# pc_shield.net
KiCad netlist of a schematic drawn in EAGLE
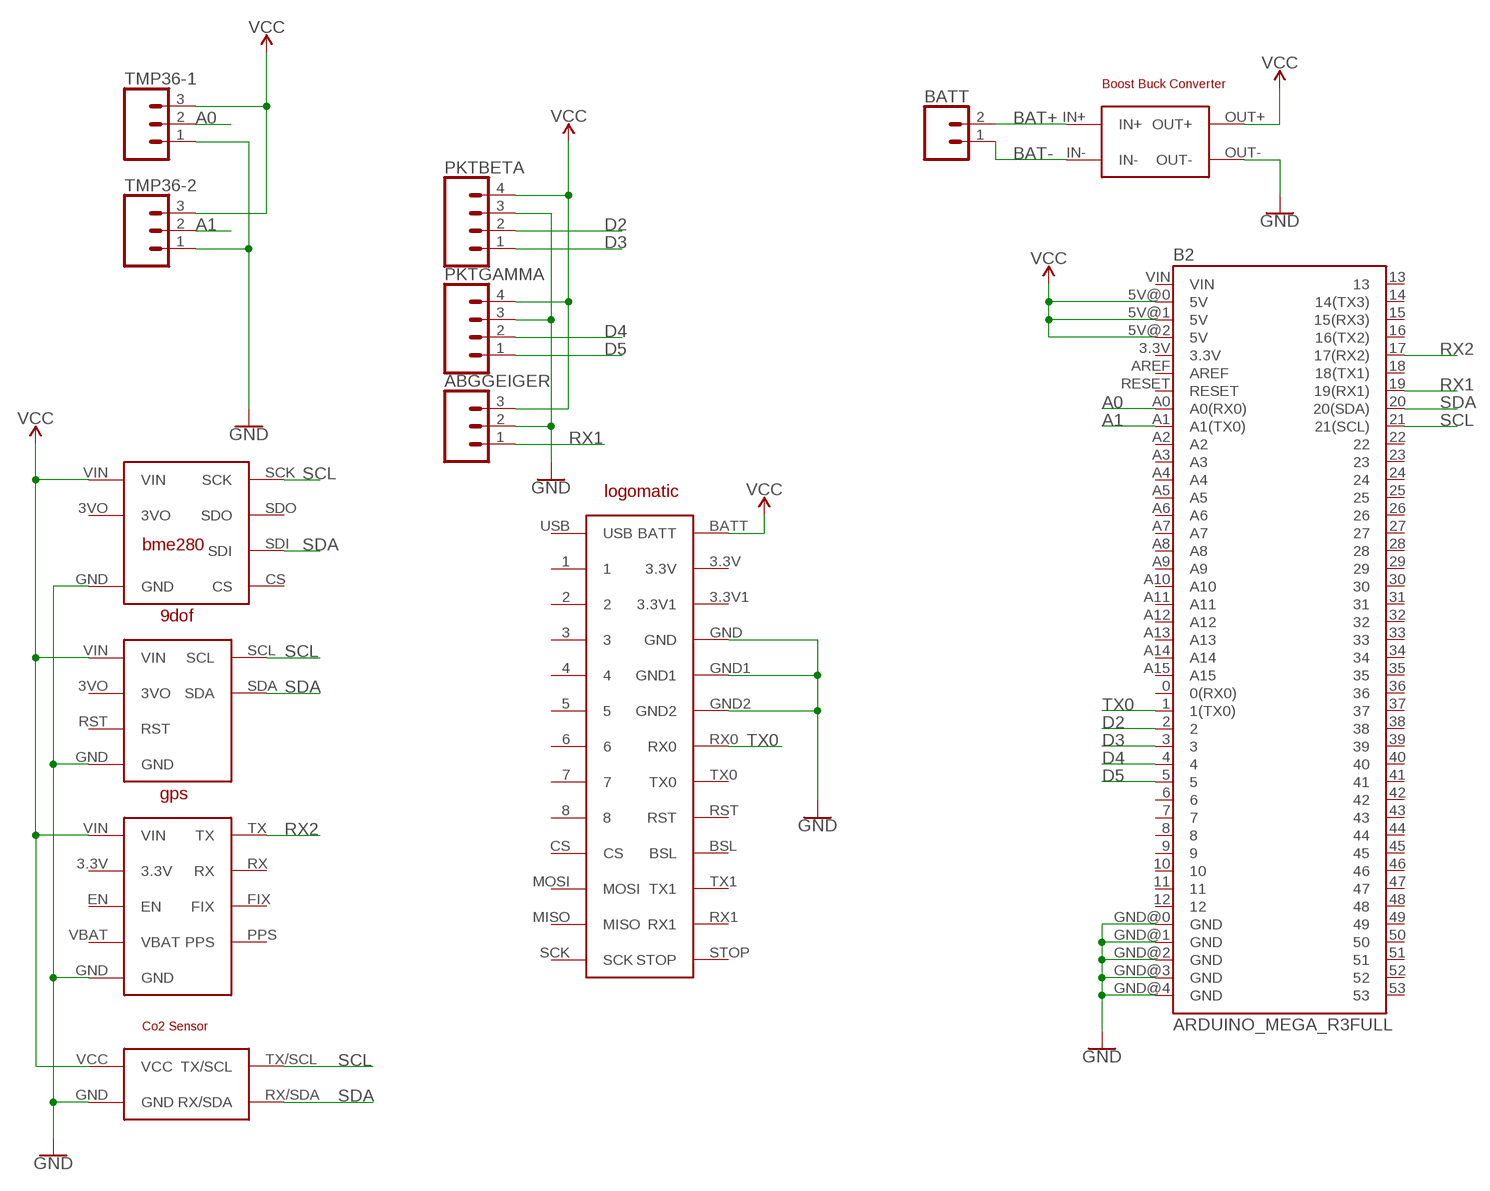
[diagram p0: schematic, sheet 1]

(export (version "E")
  (design (tool "Eeschema 10.0.6"))
  (components
    (comp (ref "ABGGEIGER")
      (value "CONN_03")
      (footprint "eagle-import:1X03")
      (libsource (lib "eagle-import") (part "CONN_03"))
    )
    (comp (ref "B2")
      (value "ARDUINO_MEGA_R3FULL")
      (footprint "eagle-import:ARDUINO_MEGA")
      (libsource (lib "eagle-import") (part "ARDUINO_MEGA_R3FULL"))
    )
    (comp (ref "BATT")
      (value "CONN_02")
      (footprint "eagle-import:1X02")
      (libsource (lib "eagle-import") (part "CONN_02"))
    )
    (comp (ref "PKTBETA")
      (value "CONN_04")
      (footprint "eagle-import:1X04")
      (libsource (lib "eagle-import") (part "CONN_04"))
    )
    (comp (ref "PKTGAMMA")
      (value "CONN_04")
      (footprint "eagle-import:1X04")
      (libsource (lib "eagle-import") (part "CONN_04"))
    )
    (comp (ref "TMP36-1")
      (value "CONN_03")
      (footprint "eagle-import:1X03")
      (libsource (lib "eagle-import") (part "CONN_03"))
    )
    (comp (ref "TMP36-2")
      (value "CONN_03")
      (footprint "eagle-import:1X03")
      (libsource (lib "eagle-import") (part "CONN_03"))
    )
    (comp (ref "U$1")
      (value "ULTIMATEGPS")
      (footprint "eagle-import:ULTIMATEGPSPKG")
      (libsource (lib "eagle-import") (part "ULTIMATEGPS"))
    )
    (comp (ref "U$2")
      (value "BME280")
      (footprint "eagle-import:BME280ADAFRUITPKG")
      (libsource (lib "eagle-import") (part "BME280"))
    )
    (comp (ref "U$3")
      (value "LOGOMATIC")
      (footprint "eagle-import:LOGOMATICPKG")
      (libsource (lib "eagle-import") (part "LOGOMATIC"))
    )
    (comp (ref "U$4")
      (value "NXP9DOF")
      (footprint "eagle-import:NXP9DOFPKG")
      (libsource (lib "eagle-import") (part "NXP9DOF"))
    )
    (comp (ref "U$5")
      (value "CO2SENSOR")
      (footprint "eagle-import:CO2INTERFACEBOARDPKG")
      (libsource (lib "eagle-import") (part "CO2SENSOR"))
    )
    (comp (ref "U$6")
      (value "BOOSTBUCK")
      (footprint "eagle-import:BOOSTBUCKPKG")
      (libsource (lib "eagle-import") (part "BOOSTBUCK"))
    )
  )
  (nets
    (net (code "1") (name "/A0") (class "Default")
      (node (ref "B2") (pin "A0") (pinfunction "A0(RX0)_A0") (pintype "bidirectional"))
      (node (ref "TMP36-1") (pin "2") (pinfunction "2_2") (pintype "passive"))
    )
    (net (code "2") (name "/A1") (class "Default")
      (node (ref "B2") (pin "A1") (pinfunction "A1(TX0)_A1") (pintype "bidirectional"))
      (node (ref "TMP36-2") (pin "2") (pinfunction "2_2") (pintype "passive"))
    )
    (net (code "3") (name "/BAT+") (class "Default")
      (node (ref "BATT") (pin "2") (pinfunction "2_2") (pintype "passive"))
      (node (ref "U$6") (pin "IN+") (pinfunction "IN+_IN+") (pintype "bidirectional"))
    )
    (net (code "4") (name "/BAT-") (class "Default")
      (node (ref "BATT") (pin "1") (pinfunction "1_1") (pintype "passive"))
      (node (ref "U$6") (pin "IN-") (pinfunction "IN-_IN-") (pintype "bidirectional"))
    )
    (net (code "5") (name "/D2") (class "Default")
      (node (ref "B2") (pin "2") (pinfunction "2_2") (pintype "bidirectional"))
      (node (ref "PKTBETA") (pin "2") (pinfunction "2_2") (pintype "passive"))
    )
    (net (code "6") (name "/D3") (class "Default")
      (node (ref "B2") (pin "3") (pinfunction "3_3") (pintype "bidirectional"))
      (node (ref "PKTBETA") (pin "1") (pinfunction "1_1") (pintype "passive"))
    )
    (net (code "7") (name "/D4") (class "Default")
      (node (ref "B2") (pin "4") (pinfunction "4_4") (pintype "bidirectional"))
      (node (ref "PKTGAMMA") (pin "2") (pinfunction "2_2") (pintype "passive"))
    )
    (net (code "8") (name "/D5") (class "Default")
      (node (ref "B2") (pin "5") (pinfunction "5_5") (pintype "bidirectional"))
      (node (ref "PKTGAMMA") (pin "1") (pinfunction "1_1") (pintype "passive"))
    )
    (net (code "9") (name "/RX1") (class "Default")
      (node (ref "ABGGEIGER") (pin "1") (pinfunction "1_1") (pintype "passive"))
      (node (ref "B2") (pin "19") (pinfunction "19(RX1)_19") (pintype "bidirectional"))
    )
    (net (code "10") (name "/RX2") (class "Default")
      (node (ref "B2") (pin "17") (pinfunction "17(RX2)_17") (pintype "bidirectional"))
      (node (ref "U$1") (pin "TX") (pinfunction "TX_TX") (pintype "bidirectional"))
    )
    (net (code "11") (name "/SCL") (class "Default")
      (node (ref "B2") (pin "21") (pinfunction "21(SCL)_21") (pintype "bidirectional"))
      (node (ref "U$2") (pin "SCK") (pinfunction "SCK_SCK") (pintype "bidirectional"))
      (node (ref "U$4") (pin "SCL") (pinfunction "SCL_SCL") (pintype "bidirectional"))
      (node (ref "U$5") (pin "TX/SCL") (pinfunction "TX/SCL_TX/SCL") (pintype "bidirectional"))
    )
    (net (code "12") (name "/SDA") (class "Default")
      (node (ref "B2") (pin "20") (pinfunction "20(SDA)_20") (pintype "bidirectional"))
      (node (ref "U$2") (pin "SDI") (pinfunction "SDI_SDI") (pintype "bidirectional"))
      (node (ref "U$4") (pin "SDA") (pinfunction "SDA_SDA") (pintype "bidirectional"))
      (node (ref "U$5") (pin "RX/SDA") (pinfunction "RX/SDA_RX/SDA") (pintype "bidirectional"))
    )
    (net (code "13") (name "/TX0") (class "Default")
      (node (ref "B2") (pin "1") (pinfunction "1(TX0)_1") (pintype "bidirectional"))
      (node (ref "U$3") (pin "RX0") (pinfunction "RX0_RX0") (pintype "bidirectional"))
    )
    (net (code "14") (name "GND") (class "Default")
      (node (ref "ABGGEIGER") (pin "2") (pinfunction "2_2") (pintype "passive"))
      (node (ref "B2") (pin "GND@0") (pinfunction "GND_GND@0") (pintype "bidirectional"))
      (node (ref "B2") (pin "GND@1") (pinfunction "GND_GND@1") (pintype "bidirectional"))
      (node (ref "B2") (pin "GND@2") (pinfunction "GND_GND@2") (pintype "bidirectional"))
      (node (ref "B2") (pin "GND@3") (pinfunction "GND_GND@3") (pintype "bidirectional"))
      (node (ref "B2") (pin "GND@4") (pinfunction "GND_GND@4") (pintype "bidirectional"))
      (node (ref "PKTBETA") (pin "3") (pinfunction "3_3") (pintype "passive"))
      (node (ref "PKTGAMMA") (pin "3") (pinfunction "3_3") (pintype "passive"))
      (node (ref "TMP36-1") (pin "1") (pinfunction "1_1") (pintype "passive"))
      (node (ref "TMP36-2") (pin "1") (pinfunction "1_1") (pintype "passive"))
      (node (ref "U$1") (pin "GND") (pinfunction "GND_GND") (pintype "bidirectional"))
      (node (ref "U$2") (pin "GND") (pinfunction "GND_GND") (pintype "bidirectional"))
      (node (ref "U$3") (pin "GND") (pinfunction "GND_GND") (pintype "bidirectional"))
      (node (ref "U$3") (pin "GND1") (pinfunction "GND1_GND1") (pintype "bidirectional"))
      (node (ref "U$3") (pin "GND2") (pinfunction "GND2_GND2") (pintype "bidirectional"))
      (node (ref "U$4") (pin "GND") (pinfunction "GND_GND") (pintype "bidirectional"))
      (node (ref "U$5") (pin "GND") (pinfunction "GND_GND") (pintype "bidirectional"))
      (node (ref "U$6") (pin "OUT-") (pinfunction "OUT-_OUT-") (pintype "bidirectional"))
    )
    (net (code "15") (name "VCC") (class "Default")
      (node (ref "ABGGEIGER") (pin "3") (pinfunction "3_3") (pintype "passive"))
      (node (ref "B2") (pin "5V@0") (pinfunction "5V_5V@0") (pintype "bidirectional"))
      (node (ref "B2") (pin "5V@1") (pinfunction "5V_5V@1") (pintype "bidirectional"))
      (node (ref "B2") (pin "5V@2") (pinfunction "5V_5V@2") (pintype "bidirectional"))
      (node (ref "PKTBETA") (pin "4") (pinfunction "4_4") (pintype "passive"))
      (node (ref "PKTGAMMA") (pin "4") (pinfunction "4_4") (pintype "passive"))
      (node (ref "TMP36-1") (pin "3") (pinfunction "3_3") (pintype "passive"))
      (node (ref "TMP36-2") (pin "3") (pinfunction "3_3") (pintype "passive"))
      (node (ref "U$1") (pin "VIN") (pinfunction "VIN_VIN") (pintype "bidirectional"))
      (node (ref "U$2") (pin "VIN") (pinfunction "VIN_VIN") (pintype "bidirectional"))
      (node (ref "U$3") (pin "BATT") (pinfunction "BATT_BATT") (pintype "bidirectional"))
      (node (ref "U$4") (pin "VIN") (pinfunction "VIN_VIN") (pintype "bidirectional"))
      (node (ref "U$5") (pin "VCC") (pinfunction "VCC_VCC") (pintype "bidirectional"))
      (node (ref "U$6") (pin "OUT+") (pinfunction "OUT+_OUT+") (pintype "bidirectional"))
    )
    (net (code "16") (name "unconnected-(B2-0(RX0)-Pad0)") (class "Default")
      (node (ref "B2") (pin "0") (pinfunction "0(RX0)_0") (pintype "bidirectional"))
    )
    (net (code "17") (name "unconnected-(B2-14(TX3)-Pad14)") (class "Default")
      (node (ref "B2") (pin "14") (pinfunction "14(TX3)_14") (pintype "bidirectional"))
    )
    (net (code "18") (name "unconnected-(B2-15(RX3)-Pad15)") (class "Default")
      (node (ref "B2") (pin "15") (pinfunction "15(RX3)_15") (pintype "bidirectional"))
    )
    (net (code "19") (name "unconnected-(B2-16(TX2)-Pad16)") (class "Default")
      (node (ref "B2") (pin "16") (pinfunction "16(TX2)_16") (pintype "bidirectional"))
    )
    (net (code "20") (name "unconnected-(B2-18(TX1)-Pad18)") (class "Default")
      (node (ref "B2") (pin "18") (pinfunction "18(TX1)_18") (pintype "bidirectional"))
    )
    (net (code "21") (name "unconnected-(B2-Pad3.3V)") (class "Default")
      (node (ref "B2") (pin "3.3V") (pinfunction "3.3V_3.3V") (pintype "bidirectional"))
    )
    (net (code "22") (name "unconnected-(B2-Pad6)") (class "Default")
      (node (ref "B2") (pin "6") (pinfunction "6_6") (pintype "bidirectional"))
    )
    (net (code "23") (name "unconnected-(B2-Pad7)") (class "Default")
      (node (ref "B2") (pin "7") (pinfunction "7_7") (pintype "bidirectional"))
    )
    (net (code "24") (name "unconnected-(B2-Pad8)") (class "Default")
      (node (ref "B2") (pin "8") (pinfunction "8_8") (pintype "bidirectional"))
    )
    (net (code "25") (name "unconnected-(B2-Pad9)") (class "Default")
      (node (ref "B2") (pin "9") (pinfunction "9_9") (pintype "bidirectional"))
    )
    (net (code "26") (name "unconnected-(B2-Pad10)") (class "Default")
      (node (ref "B2") (pin "10") (pinfunction "10_10") (pintype "bidirectional"))
    )
    (net (code "27") (name "unconnected-(B2-Pad11)") (class "Default")
      (node (ref "B2") (pin "11") (pinfunction "11_11") (pintype "bidirectional"))
    )
    (net (code "28") (name "unconnected-(B2-Pad12)") (class "Default")
      (node (ref "B2") (pin "12") (pinfunction "12_12") (pintype "bidirectional"))
    )
    (net (code "29") (name "unconnected-(B2-Pad13)") (class "Default")
      (node (ref "B2") (pin "13") (pinfunction "13_13") (pintype "bidirectional"))
    )
    (net (code "30") (name "unconnected-(B2-Pad22)") (class "Default")
      (node (ref "B2") (pin "22") (pinfunction "22_22") (pintype "bidirectional"))
    )
    (net (code "31") (name "unconnected-(B2-Pad23)") (class "Default")
      (node (ref "B2") (pin "23") (pinfunction "23_23") (pintype "bidirectional"))
    )
    (net (code "32") (name "unconnected-(B2-Pad24)") (class "Default")
      (node (ref "B2") (pin "24") (pinfunction "24_24") (pintype "bidirectional"))
    )
    (net (code "33") (name "unconnected-(B2-Pad25)") (class "Default")
      (node (ref "B2") (pin "25") (pinfunction "25_25") (pintype "bidirectional"))
    )
    (net (code "34") (name "unconnected-(B2-Pad26)") (class "Default")
      (node (ref "B2") (pin "26") (pinfunction "26_26") (pintype "bidirectional"))
    )
    (net (code "35") (name "unconnected-(B2-Pad27)") (class "Default")
      (node (ref "B2") (pin "27") (pinfunction "27_27") (pintype "bidirectional"))
    )
    (net (code "36") (name "unconnected-(B2-Pad28)") (class "Default")
      (node (ref "B2") (pin "28") (pinfunction "28_28") (pintype "bidirectional"))
    )
    (net (code "37") (name "unconnected-(B2-Pad29)") (class "Default")
      (node (ref "B2") (pin "29") (pinfunction "29_29") (pintype "bidirectional"))
    )
    (net (code "38") (name "unconnected-(B2-Pad30)") (class "Default")
      (node (ref "B2") (pin "30") (pinfunction "30_30") (pintype "bidirectional"))
    )
    (net (code "39") (name "unconnected-(B2-Pad31)") (class "Default")
      (node (ref "B2") (pin "31") (pinfunction "31_31") (pintype "bidirectional"))
    )
    (net (code "40") (name "unconnected-(B2-Pad32)") (class "Default")
      (node (ref "B2") (pin "32") (pinfunction "32_32") (pintype "bidirectional"))
    )
    (net (code "41") (name "unconnected-(B2-Pad33)") (class "Default")
      (node (ref "B2") (pin "33") (pinfunction "33_33") (pintype "bidirectional"))
    )
    (net (code "42") (name "unconnected-(B2-Pad34)") (class "Default")
      (node (ref "B2") (pin "34") (pinfunction "34_34") (pintype "bidirectional"))
    )
    (net (code "43") (name "unconnected-(B2-Pad35)") (class "Default")
      (node (ref "B2") (pin "35") (pinfunction "35_35") (pintype "bidirectional"))
    )
    (net (code "44") (name "unconnected-(B2-Pad36)") (class "Default")
      (node (ref "B2") (pin "36") (pinfunction "36_36") (pintype "bidirectional"))
    )
    (net (code "45") (name "unconnected-(B2-Pad37)") (class "Default")
      (node (ref "B2") (pin "37") (pinfunction "37_37") (pintype "bidirectional"))
    )
    (net (code "46") (name "unconnected-(B2-Pad38)") (class "Default")
      (node (ref "B2") (pin "38") (pinfunction "38_38") (pintype "bidirectional"))
    )
    (net (code "47") (name "unconnected-(B2-Pad39)") (class "Default")
      (node (ref "B2") (pin "39") (pinfunction "39_39") (pintype "bidirectional"))
    )
    (net (code "48") (name "unconnected-(B2-Pad40)") (class "Default")
      (node (ref "B2") (pin "40") (pinfunction "40_40") (pintype "bidirectional"))
    )
    (net (code "49") (name "unconnected-(B2-Pad41)") (class "Default")
      (node (ref "B2") (pin "41") (pinfunction "41_41") (pintype "bidirectional"))
    )
    (net (code "50") (name "unconnected-(B2-Pad42)") (class "Default")
      (node (ref "B2") (pin "42") (pinfunction "42_42") (pintype "bidirectional"))
    )
    (net (code "51") (name "unconnected-(B2-Pad43)") (class "Default")
      (node (ref "B2") (pin "43") (pinfunction "43_43") (pintype "bidirectional"))
    )
    (net (code "52") (name "unconnected-(B2-Pad44)") (class "Default")
      (node (ref "B2") (pin "44") (pinfunction "44_44") (pintype "bidirectional"))
    )
    (net (code "53") (name "unconnected-(B2-Pad45)") (class "Default")
      (node (ref "B2") (pin "45") (pinfunction "45_45") (pintype "bidirectional"))
    )
    (net (code "54") (name "unconnected-(B2-Pad46)") (class "Default")
      (node (ref "B2") (pin "46") (pinfunction "46_46") (pintype "bidirectional"))
    )
    (net (code "55") (name "unconnected-(B2-Pad47)") (class "Default")
      (node (ref "B2") (pin "47") (pinfunction "47_47") (pintype "bidirectional"))
    )
    (net (code "56") (name "unconnected-(B2-Pad48)") (class "Default")
      (node (ref "B2") (pin "48") (pinfunction "48_48") (pintype "bidirectional"))
    )
    (net (code "57") (name "unconnected-(B2-Pad49)") (class "Default")
      (node (ref "B2") (pin "49") (pinfunction "49_49") (pintype "bidirectional"))
    )
    (net (code "58") (name "unconnected-(B2-Pad50)") (class "Default")
      (node (ref "B2") (pin "50") (pinfunction "50_50") (pintype "bidirectional"))
    )
    (net (code "59") (name "unconnected-(B2-Pad51)") (class "Default")
      (node (ref "B2") (pin "51") (pinfunction "51_51") (pintype "bidirectional"))
    )
    (net (code "60") (name "unconnected-(B2-Pad52)") (class "Default")
      (node (ref "B2") (pin "52") (pinfunction "52_52") (pintype "bidirectional"))
    )
    (net (code "61") (name "unconnected-(B2-Pad53)") (class "Default")
      (node (ref "B2") (pin "53") (pinfunction "53_53") (pintype "bidirectional"))
    )
    (net (code "62") (name "unconnected-(B2-PadA2)") (class "Default")
      (node (ref "B2") (pin "A2") (pinfunction "A2_A2") (pintype "bidirectional"))
    )
    (net (code "63") (name "unconnected-(B2-PadA3)") (class "Default")
      (node (ref "B2") (pin "A3") (pinfunction "A3_A3") (pintype "bidirectional"))
    )
    (net (code "64") (name "unconnected-(B2-PadA4)") (class "Default")
      (node (ref "B2") (pin "A4") (pinfunction "A4_A4") (pintype "bidirectional"))
    )
    (net (code "65") (name "unconnected-(B2-PadA5)") (class "Default")
      (node (ref "B2") (pin "A5") (pinfunction "A5_A5") (pintype "bidirectional"))
    )
    (net (code "66") (name "unconnected-(B2-PadA6)") (class "Default")
      (node (ref "B2") (pin "A6") (pinfunction "A6_A6") (pintype "bidirectional"))
    )
    (net (code "67") (name "unconnected-(B2-PadA7)") (class "Default")
      (node (ref "B2") (pin "A7") (pinfunction "A7_A7") (pintype "bidirectional"))
    )
    (net (code "68") (name "unconnected-(B2-PadA8)") (class "Default")
      (node (ref "B2") (pin "A8") (pinfunction "A8_A8") (pintype "bidirectional"))
    )
    (net (code "69") (name "unconnected-(B2-PadA9)") (class "Default")
      (node (ref "B2") (pin "A9") (pinfunction "A9_A9") (pintype "bidirectional"))
    )
    (net (code "70") (name "unconnected-(B2-PadA10)") (class "Default")
      (node (ref "B2") (pin "A10") (pinfunction "A10_A10") (pintype "bidirectional"))
    )
    (net (code "71") (name "unconnected-(B2-PadA11)") (class "Default")
      (node (ref "B2") (pin "A11") (pinfunction "A11_A11") (pintype "bidirectional"))
    )
    (net (code "72") (name "unconnected-(B2-PadA12)") (class "Default")
      (node (ref "B2") (pin "A12") (pinfunction "A12_A12") (pintype "bidirectional"))
    )
    (net (code "73") (name "unconnected-(B2-PadA13)") (class "Default")
      (node (ref "B2") (pin "A13") (pinfunction "A13_A13") (pintype "bidirectional"))
    )
    (net (code "74") (name "unconnected-(B2-PadA14)") (class "Default")
      (node (ref "B2") (pin "A14") (pinfunction "A14_A14") (pintype "bidirectional"))
    )
    (net (code "75") (name "unconnected-(B2-PadA15)") (class "Default")
      (node (ref "B2") (pin "A15") (pinfunction "A15_A15") (pintype "bidirectional"))
    )
    (net (code "76") (name "unconnected-(B2-PadAREF)") (class "Default")
      (node (ref "B2") (pin "AREF") (pinfunction "AREF_AREF") (pintype "bidirectional"))
    )
    (net (code "77") (name "unconnected-(B2-PadRESET)") (class "Default")
      (node (ref "B2") (pin "RESET") (pinfunction "RESET_RESET") (pintype "bidirectional"))
    )
    (net (code "78") (name "unconnected-(B2-PadVIN)") (class "Default")
      (node (ref "B2") (pin "VIN") (pinfunction "VIN_VIN") (pintype "bidirectional"))
    )
    (net (code "79") (name "unconnected-(U$1-Pad3.3V)") (class "Default")
      (node (ref "U$1") (pin "3.3V") (pinfunction "3.3V_3.3V") (pintype "bidirectional"))
    )
    (net (code "80") (name "unconnected-(U$1-PadEN)") (class "Default")
      (node (ref "U$1") (pin "EN") (pinfunction "EN_EN") (pintype "bidirectional"))
    )
    (net (code "81") (name "unconnected-(U$1-PadFIX)") (class "Default")
      (node (ref "U$1") (pin "FIX") (pinfunction "FIX_FIX") (pintype "bidirectional"))
    )
    (net (code "82") (name "unconnected-(U$1-PadPPS)") (class "Default")
      (node (ref "U$1") (pin "PPS") (pinfunction "PPS_PPS") (pintype "bidirectional"))
    )
    (net (code "83") (name "unconnected-(U$1-PadRX)") (class "Default")
      (node (ref "U$1") (pin "RX") (pinfunction "RX_RX") (pintype "bidirectional"))
    )
    (net (code "84") (name "unconnected-(U$1-PadVBAT)") (class "Default")
      (node (ref "U$1") (pin "VBAT") (pinfunction "VBAT_VBAT") (pintype "bidirectional"))
    )
    (net (code "85") (name "unconnected-(U$2-Pad3VO)") (class "Default")
      (node (ref "U$2") (pin "3VO") (pinfunction "3VO_3VO") (pintype "bidirectional"))
    )
    (net (code "86") (name "unconnected-(U$2-PadCS)") (class "Default")
      (node (ref "U$2") (pin "CS") (pinfunction "CS_CS") (pintype "bidirectional"))
    )
    (net (code "87") (name "unconnected-(U$2-PadSDO)") (class "Default")
      (node (ref "U$2") (pin "SDO") (pinfunction "SDO_SDO") (pintype "bidirectional"))
    )
    (net (code "88") (name "unconnected-(U$3-Pad1)") (class "Default")
      (node (ref "U$3") (pin "1") (pinfunction "1_1") (pintype "bidirectional"))
    )
    (net (code "89") (name "unconnected-(U$3-Pad2)") (class "Default")
      (node (ref "U$3") (pin "2") (pinfunction "2_2") (pintype "bidirectional"))
    )
    (net (code "90") (name "unconnected-(U$3-Pad3)") (class "Default")
      (node (ref "U$3") (pin "3") (pinfunction "3_3") (pintype "bidirectional"))
    )
    (net (code "91") (name "unconnected-(U$3-Pad3.3V)") (class "Default")
      (node (ref "U$3") (pin "3.3V") (pinfunction "3.3V_3.3V") (pintype "bidirectional"))
    )
    (net (code "92") (name "unconnected-(U$3-Pad3.3V1)") (class "Default")
      (node (ref "U$3") (pin "3.3V1") (pinfunction "3.3V1_3.3V1") (pintype "bidirectional"))
    )
    (net (code "93") (name "unconnected-(U$3-Pad4)") (class "Default")
      (node (ref "U$3") (pin "4") (pinfunction "4_4") (pintype "bidirectional"))
    )
    (net (code "94") (name "unconnected-(U$3-Pad5)") (class "Default")
      (node (ref "U$3") (pin "5") (pinfunction "5_5") (pintype "bidirectional"))
    )
    (net (code "95") (name "unconnected-(U$3-Pad6)") (class "Default")
      (node (ref "U$3") (pin "6") (pinfunction "6_6") (pintype "bidirectional"))
    )
    (net (code "96") (name "unconnected-(U$3-Pad7)") (class "Default")
      (node (ref "U$3") (pin "7") (pinfunction "7_7") (pintype "bidirectional"))
    )
    (net (code "97") (name "unconnected-(U$3-Pad8)") (class "Default")
      (node (ref "U$3") (pin "8") (pinfunction "8_8") (pintype "bidirectional"))
    )
    (net (code "98") (name "unconnected-(U$3-PadBSL)") (class "Default")
      (node (ref "U$3") (pin "BSL") (pinfunction "BSL_BSL") (pintype "bidirectional"))
    )
    (net (code "99") (name "unconnected-(U$3-PadCS)") (class "Default")
      (node (ref "U$3") (pin "CS") (pinfunction "CS_CS") (pintype "bidirectional"))
    )
    (net (code "100") (name "unconnected-(U$3-PadMISO)") (class "Default")
      (node (ref "U$3") (pin "MISO") (pinfunction "MISO_MISO") (pintype "bidirectional"))
    )
    (net (code "101") (name "unconnected-(U$3-PadMOSI)") (class "Default")
      (node (ref "U$3") (pin "MOSI") (pinfunction "MOSI_MOSI") (pintype "bidirectional"))
    )
    (net (code "102") (name "unconnected-(U$3-PadRST)") (class "Default")
      (node (ref "U$3") (pin "RST") (pinfunction "RST_RST") (pintype "bidirectional"))
    )
    (net (code "103") (name "unconnected-(U$3-PadRX1)") (class "Default")
      (node (ref "U$3") (pin "RX1") (pinfunction "RX1_RX1") (pintype "bidirectional"))
    )
    (net (code "104") (name "unconnected-(U$3-PadSCK)") (class "Default")
      (node (ref "U$3") (pin "SCK") (pinfunction "SCK_SCK") (pintype "bidirectional"))
    )
    (net (code "105") (name "unconnected-(U$3-PadSTOP)") (class "Default")
      (node (ref "U$3") (pin "STOP") (pinfunction "STOP_STOP") (pintype "bidirectional"))
    )
    (net (code "106") (name "unconnected-(U$3-PadTX0)") (class "Default")
      (node (ref "U$3") (pin "TX0") (pinfunction "TX0_TX0") (pintype "bidirectional"))
    )
    (net (code "107") (name "unconnected-(U$3-PadTX1)") (class "Default")
      (node (ref "U$3") (pin "TX1") (pinfunction "TX1_TX1") (pintype "bidirectional"))
    )
    (net (code "108") (name "unconnected-(U$3-PadUSB)") (class "Default")
      (node (ref "U$3") (pin "USB") (pinfunction "USB_USB") (pintype "bidirectional"))
    )
    (net (code "109") (name "unconnected-(U$4-Pad3VO)") (class "Default")
      (node (ref "U$4") (pin "3VO") (pinfunction "3VO_3VO") (pintype "bidirectional"))
    )
    (net (code "110") (name "unconnected-(U$4-PadRST)") (class "Default")
      (node (ref "U$4") (pin "RST") (pinfunction "RST_RST") (pintype "bidirectional"))
    )
  )
)
